# input-selector.net
KiCad netlist of a schematic drawn in EAGLE
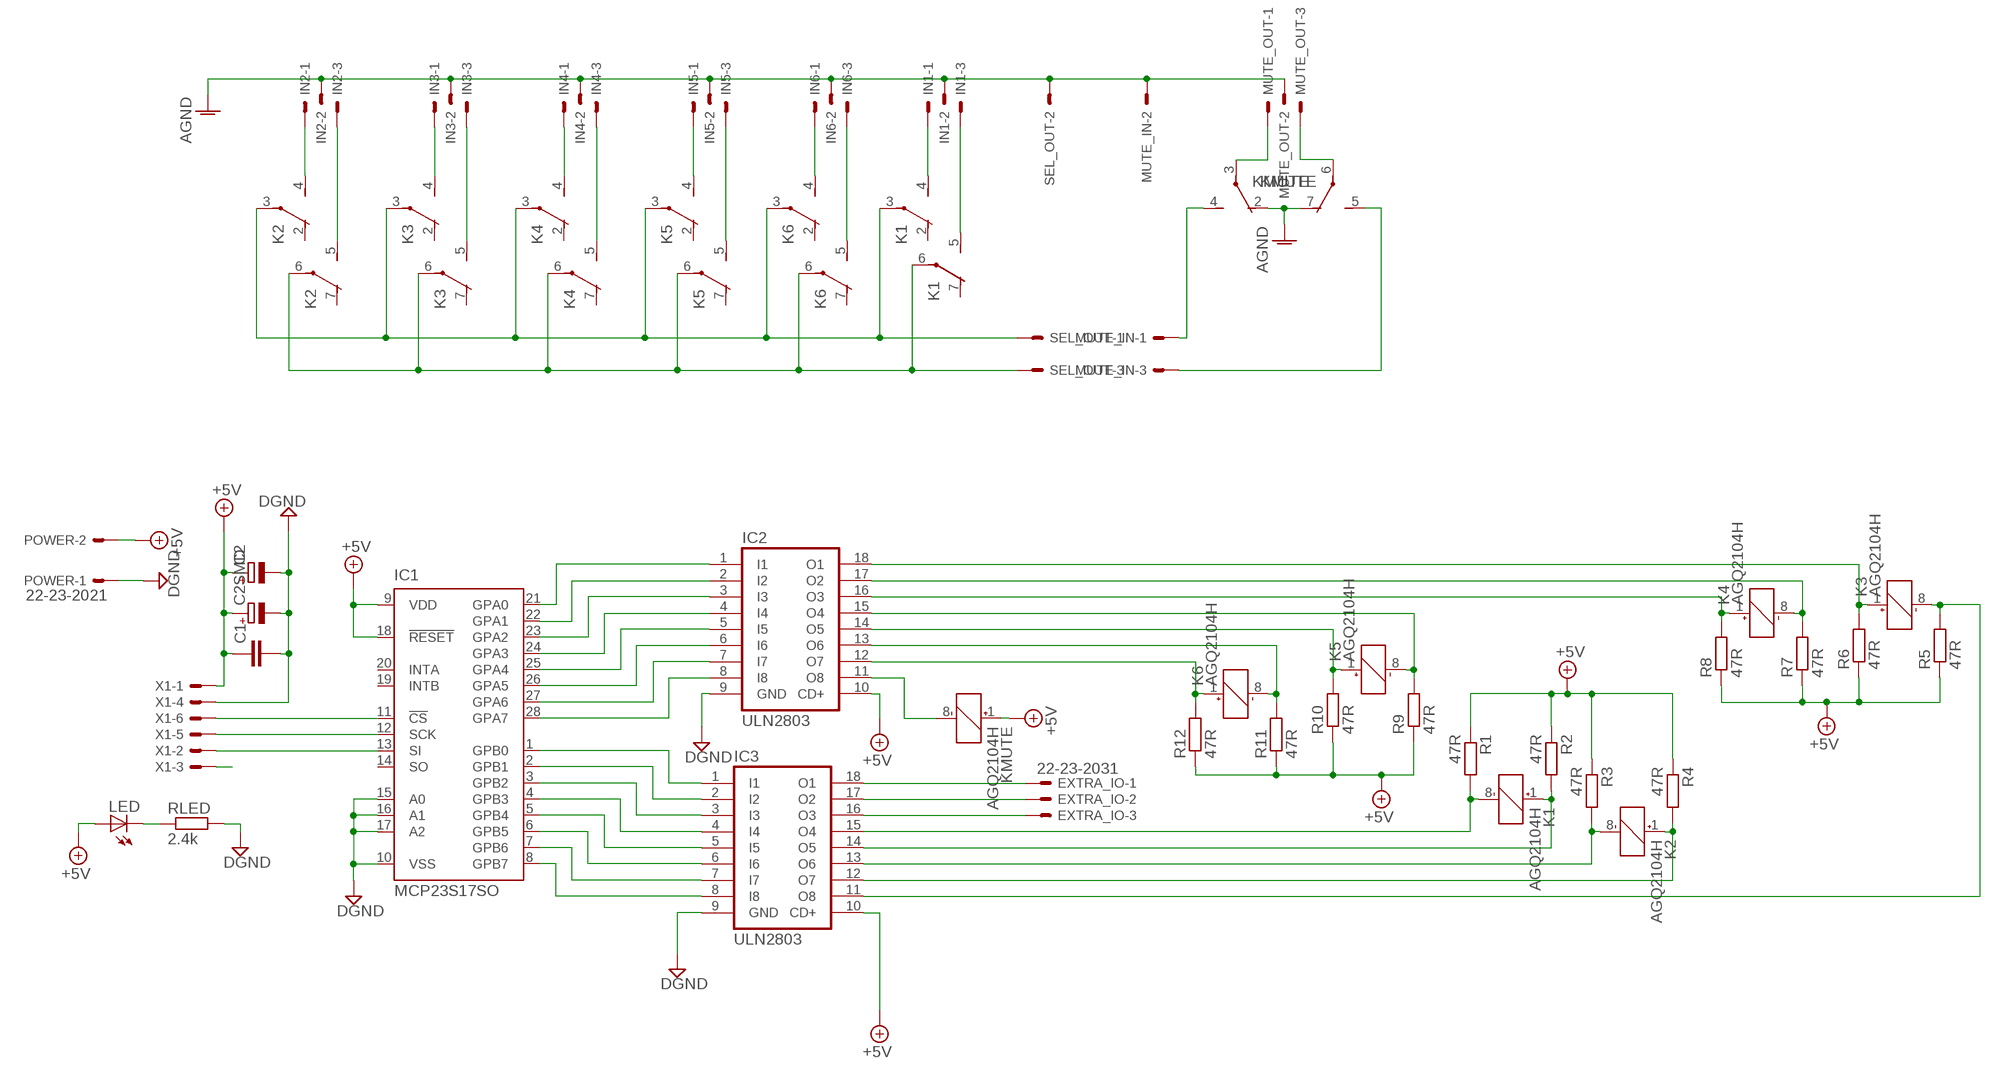
[diagram p0: schematic, sheet 1]

(export (version "E")
  (design (tool "Eeschema 10.0.6"))
  (components
    (comp (ref "C1")
      (value "C-EUC1206")
      (footprint "eagle-import:C1206")
      (libsource (lib "eagle-import") (part "C-EUC1206"))
    )
    (comp (ref "C2")
      (value "CPOL-EUE3.5-8")
      (footprint "eagle-import:E3,5-8")
      (libsource (lib "eagle-import") (part "CPOL-EUE3.5-8"))
    )
    (comp (ref "C2SMD")
      (value "CPOL-EUE")
      (footprint "eagle-import:PANASONIC_E")
      (libsource (lib "eagle-import") (part "CPOL-EUE"))
    )
    (comp (ref "EXTRA_IO")
      (value "22-23-2031")
      (footprint "eagle-import:22-23-2031")
      (fields (field (name "MF") "MOLEX"))
      (libsource (lib "eagle-import") (part "22-23-2031"))
    )
    (comp (ref "IC1")
      (value "MCP23S17SO")
      (footprint "eagle-import:SO28W")
      (fields (field (name "MF") "MICROCHIP") (field (name "MPN") "MCP23S17-E/SO"))
      (libsource (lib "eagle-import") (part "MCP23S17SO"))
    )
    (comp (ref "IC2")
      (value "ULN2803")
      (footprint "eagle-import:SO-18W")
      (libsource (lib "eagle-import") (part "ULN2803ADW"))
    )
    (comp (ref "IC3")
      (value "ULN2803")
      (footprint "eagle-import:SO-18W")
      (libsource (lib "eagle-import") (part "ULN2803ADW"))
    )
    (comp (ref "IN1")
      (value "22-23-2031")
      (footprint "eagle-import:22-23-2031")
      (fields (field (name "MF") "MOLEX"))
      (libsource (lib "eagle-import") (part "22-23-2031"))
    )
    (comp (ref "IN2")
      (value "22-23-2031")
      (footprint "eagle-import:22-23-2031")
      (fields (field (name "MF") "MOLEX"))
      (libsource (lib "eagle-import") (part "22-23-2031"))
    )
    (comp (ref "IN3")
      (value "22-23-2031")
      (footprint "eagle-import:22-23-2031")
      (fields (field (name "MF") "MOLEX"))
      (libsource (lib "eagle-import") (part "22-23-2031"))
    )
    (comp (ref "IN4")
      (value "22-23-2031")
      (footprint "eagle-import:22-23-2031")
      (fields (field (name "MF") "MOLEX"))
      (libsource (lib "eagle-import") (part "22-23-2031"))
    )
    (comp (ref "IN5")
      (value "22-23-2031")
      (footprint "eagle-import:22-23-2031")
      (fields (field (name "MF") "MOLEX"))
      (libsource (lib "eagle-import") (part "22-23-2031"))
    )
    (comp (ref "IN6")
      (value "22-23-2031")
      (footprint "eagle-import:22-23-2031")
      (fields (field (name "MF") "MOLEX"))
      (libsource (lib "eagle-import") (part "22-23-2031"))
    )
    (comp (ref "K1")
      (value "AGQ2104H")
      (footprint "eagle-import:PCBBOARD")
      (libsource (lib "eagle-import") (part "AGQ2104H"))
    )
    (comp (ref "K2")
      (value "AGQ2104H")
      (footprint "eagle-import:PCBBOARD")
      (libsource (lib "eagle-import") (part "AGQ2104H"))
    )
    (comp (ref "K3")
      (value "AGQ2104H")
      (footprint "eagle-import:PCBBOARD")
      (libsource (lib "eagle-import") (part "AGQ2104H"))
    )
    (comp (ref "K4")
      (value "AGQ2104H")
      (footprint "eagle-import:PCBBOARD")
      (libsource (lib "eagle-import") (part "AGQ2104H"))
    )
    (comp (ref "K5")
      (value "AGQ2104H")
      (footprint "eagle-import:PCBBOARD")
      (libsource (lib "eagle-import") (part "AGQ2104H"))
    )
    (comp (ref "K6")
      (value "AGQ2104H")
      (footprint "eagle-import:PCBBOARD")
      (libsource (lib "eagle-import") (part "AGQ2104H"))
    )
    (comp (ref "KMUTE")
      (value "AGQ2104H")
      (footprint "eagle-import:PCBBOARD")
      (libsource (lib "eagle-import") (part "AGQ2104H"))
    )
    (comp (ref "LED")
      (value "LEDSMT1206")
      (footprint "eagle-import:1206")
      (libsource (lib "eagle-import") (part "LEDSMT1206"))
    )
    (comp (ref "MUTE_IN")
      (value "22-23-2031")
      (footprint "eagle-import:22-23-2031")
      (fields (field (name "MF") "MOLEX"))
      (libsource (lib "eagle-import") (part "22-23-2031"))
    )
    (comp (ref "MUTE_OUT")
      (value "22-23-2031")
      (footprint "eagle-import:22-23-2031")
      (fields (field (name "MF") "MOLEX"))
      (libsource (lib "eagle-import") (part "22-23-2031"))
    )
    (comp (ref "POWER")
      (value "22-23-2021")
      (footprint "eagle-import:22-23-2021")
      (fields (field (name "MF") "MOLEX"))
      (libsource (lib "eagle-import") (part "22-23-2021"))
    )
    (comp (ref "R1")
      (value "47R")
      (footprint "eagle-import:R1206")
      (libsource (lib "eagle-import") (part "R-EU_R1206"))
    )
    (comp (ref "R2")
      (value "47R")
      (footprint "eagle-import:R1206")
      (libsource (lib "eagle-import") (part "R-EU_R1206"))
    )
    (comp (ref "R3")
      (value "47R")
      (footprint "eagle-import:R1206")
      (libsource (lib "eagle-import") (part "R-EU_R1206"))
    )
    (comp (ref "R4")
      (value "47R")
      (footprint "eagle-import:R1206")
      (libsource (lib "eagle-import") (part "R-EU_R1206"))
    )
    (comp (ref "R5")
      (value "47R")
      (footprint "eagle-import:R1206")
      (libsource (lib "eagle-import") (part "R-EU_R1206"))
    )
    (comp (ref "R6")
      (value "47R")
      (footprint "eagle-import:R1206")
      (libsource (lib "eagle-import") (part "R-EU_R1206"))
    )
    (comp (ref "R7")
      (value "47R")
      (footprint "eagle-import:R1206")
      (libsource (lib "eagle-import") (part "R-EU_R1206"))
    )
    (comp (ref "R8")
      (value "47R")
      (footprint "eagle-import:R1206")
      (libsource (lib "eagle-import") (part "R-EU_R1206"))
    )
    (comp (ref "R9")
      (value "47R")
      (footprint "eagle-import:R1206")
      (libsource (lib "eagle-import") (part "R-EU_R1206"))
    )
    (comp (ref "R10")
      (value "47R")
      (footprint "eagle-import:R1206")
      (libsource (lib "eagle-import") (part "R-EU_R1206"))
    )
    (comp (ref "R11")
      (value "47R")
      (footprint "eagle-import:R1206")
      (libsource (lib "eagle-import") (part "R-EU_R1206"))
    )
    (comp (ref "R12")
      (value "47R")
      (footprint "eagle-import:R1206")
      (libsource (lib "eagle-import") (part "R-EU_R1206"))
    )
    (comp (ref "RLED")
      (value "2.4k")
      (footprint "eagle-import:R1206")
      (libsource (lib "eagle-import") (part "R-EU_R1206"))
    )
    (comp (ref "SEL_OUT")
      (value "22-23-2031")
      (footprint "eagle-import:22-23-2031")
      (fields (field (name "MF") "MOLEX"))
      (libsource (lib "eagle-import") (part "22-23-2031"))
    )
    (comp (ref "X1")
      (value "22-23-2061")
      (footprint "eagle-import:22-23-2061")
      (fields (field (name "MF") "MOLEX"))
      (libsource (lib "eagle-import") (part "22-23-2061"))
    )
  )
  (nets
    (net (code "1") (name "+5V") (class "Default")
      (node (ref "C1") (pin "1") (pinfunction "1_1") (pintype "passive"))
      (node (ref "C2") (pin "+") (pinfunction "+_+") (pintype "passive"))
      (node (ref "C2SMD") (pin "+") (pinfunction "+_+") (pintype "passive"))
      (node (ref "IC1") (pin "18") (pinfunction "~{RESET}_18") (pintype "input"))
      (node (ref "IC1") (pin "9") (pinfunction "VDD_9") (pintype "power_in"))
      (node (ref "IC2") (pin "10") (pinfunction "CD+_10") (pintype "passive"))
      (node (ref "IC3") (pin "10") (pinfunction "CD+_10") (pintype "passive"))
      (node (ref "KMUTE") (pin "1") (pinfunction "+_1") (pintype "passive"))
      (node (ref "LED") (pin "A") (pinfunction "A_A") (pintype "passive"))
      (node (ref "POWER") (pin "2") (pinfunction "S_2") (pintype "passive"))
      (node (ref "R1") (pin "1") (pinfunction "1_1") (pintype "passive"))
      (node (ref "R10") (pin "1") (pinfunction "1_1") (pintype "passive"))
      (node (ref "R11") (pin "1") (pinfunction "1_1") (pintype "passive"))
      (node (ref "R12") (pin "1") (pinfunction "1_1") (pintype "passive"))
      (node (ref "R2") (pin "1") (pinfunction "1_1") (pintype "passive"))
      (node (ref "R3") (pin "1") (pinfunction "1_1") (pintype "passive"))
      (node (ref "R4") (pin "1") (pinfunction "1_1") (pintype "passive"))
      (node (ref "R5") (pin "1") (pinfunction "1_1") (pintype "passive"))
      (node (ref "R6") (pin "1") (pinfunction "1_1") (pintype "passive"))
      (node (ref "R7") (pin "1") (pinfunction "1_1") (pintype "passive"))
      (node (ref "R8") (pin "1") (pinfunction "1_1") (pintype "passive"))
      (node (ref "R9") (pin "1") (pinfunction "1_1") (pintype "passive"))
      (node (ref "X1") (pin "1") (pinfunction "S_1") (pintype "passive"))
    )
    (net (code "2") (name "AGND") (class "Default")
      (node (ref "IN1") (pin "2") (pinfunction "S_2") (pintype "passive"))
      (node (ref "IN2") (pin "2") (pinfunction "S_2") (pintype "passive"))
      (node (ref "IN3") (pin "2") (pinfunction "S_2") (pintype "passive"))
      (node (ref "IN4") (pin "2") (pinfunction "S_2") (pintype "passive"))
      (node (ref "IN5") (pin "2") (pinfunction "S_2") (pintype "passive"))
      (node (ref "IN6") (pin "2") (pinfunction "S_2") (pintype "passive"))
      (node (ref "KMUTE") (pin "2") (pinfunction "O_2") (pintype "passive"))
      (node (ref "KMUTE") (pin "7") (pinfunction "O_7") (pintype "passive"))
      (node (ref "MUTE_IN") (pin "2") (pinfunction "S_2") (pintype "passive"))
      (node (ref "MUTE_OUT") (pin "2") (pinfunction "S_2") (pintype "passive"))
      (node (ref "SEL_OUT") (pin "2") (pinfunction "S_2") (pintype "passive"))
    )
    (net (code "3") (name "DGND") (class "Default")
      (node (ref "C1") (pin "2") (pinfunction "2_2") (pintype "passive"))
      (node (ref "C2") (pin "-") (pinfunction "-_-") (pintype "passive"))
      (node (ref "C2SMD") (pin "-") (pinfunction "-_-") (pintype "passive"))
      (node (ref "IC1") (pin "10") (pinfunction "VSS_10") (pintype "power_in"))
      (node (ref "IC1") (pin "15") (pinfunction "A0_15") (pintype "input"))
      (node (ref "IC1") (pin "16") (pinfunction "A1_16") (pintype "input"))
      (node (ref "IC1") (pin "17") (pinfunction "A2_17") (pintype "input"))
      (node (ref "IC2") (pin "9") (pinfunction "GND_9") (pintype "power_in"))
      (node (ref "IC3") (pin "9") (pinfunction "GND_9") (pintype "power_in"))
      (node (ref "POWER") (pin "1") (pinfunction "S_1") (pintype "passive"))
      (node (ref "RLED") (pin "2") (pinfunction "2_2") (pintype "passive"))
      (node (ref "X1") (pin "4") (pinfunction "S_4") (pintype "passive"))
    )
    (net (code "4") (name "Net-(EXTRA_IOA-S)") (class "Default")
      (node (ref "EXTRA_IO") (pin "1") (pinfunction "S_1") (pintype "passive"))
      (node (ref "IC3") (pin "18") (pinfunction "O1_18") (pintype "open_collector"))
    )
    (net (code "5") (name "Net-(EXTRA_IOB-S)") (class "Default")
      (node (ref "EXTRA_IO") (pin "2") (pinfunction "S_2") (pintype "passive"))
      (node (ref "IC3") (pin "17") (pinfunction "O2_17") (pintype "open_collector"))
    )
    (net (code "6") (name "Net-(EXTRA_IOC-S)") (class "Default")
      (node (ref "EXTRA_IO") (pin "3") (pinfunction "S_3") (pintype "passive"))
      (node (ref "IC3") (pin "16") (pinfunction "O3_16") (pintype "open_collector"))
    )
    (net (code "7") (name "Net-(IC1-GPA0)") (class "Default")
      (node (ref "IC1") (pin "21") (pinfunction "GPA0_21") (pintype "bidirectional"))
      (node (ref "IC2") (pin "1") (pinfunction "I1_1") (pintype "input"))
    )
    (net (code "8") (name "Net-(IC1-GPA1)") (class "Default")
      (node (ref "IC1") (pin "22") (pinfunction "GPA1_22") (pintype "bidirectional"))
      (node (ref "IC2") (pin "2") (pinfunction "I2_2") (pintype "input"))
    )
    (net (code "9") (name "Net-(IC1-GPA2)") (class "Default")
      (node (ref "IC1") (pin "23") (pinfunction "GPA2_23") (pintype "bidirectional"))
      (node (ref "IC2") (pin "3") (pinfunction "I3_3") (pintype "input"))
    )
    (net (code "10") (name "Net-(IC1-GPA3)") (class "Default")
      (node (ref "IC1") (pin "24") (pinfunction "GPA3_24") (pintype "bidirectional"))
      (node (ref "IC2") (pin "4") (pinfunction "I4_4") (pintype "input"))
    )
    (net (code "11") (name "Net-(IC1-GPA4)") (class "Default")
      (node (ref "IC1") (pin "25") (pinfunction "GPA4_25") (pintype "bidirectional"))
      (node (ref "IC2") (pin "5") (pinfunction "I5_5") (pintype "input"))
    )
    (net (code "12") (name "Net-(IC1-GPA5)") (class "Default")
      (node (ref "IC1") (pin "26") (pinfunction "GPA5_26") (pintype "bidirectional"))
      (node (ref "IC2") (pin "6") (pinfunction "I6_6") (pintype "input"))
    )
    (net (code "13") (name "Net-(IC1-GPA6)") (class "Default")
      (node (ref "IC1") (pin "27") (pinfunction "GPA6_27") (pintype "bidirectional"))
      (node (ref "IC2") (pin "7") (pinfunction "I7_7") (pintype "input"))
    )
    (net (code "14") (name "Net-(IC1-GPA7)") (class "Default")
      (node (ref "IC1") (pin "28") (pinfunction "GPA7_28") (pintype "bidirectional"))
      (node (ref "IC2") (pin "8") (pinfunction "I8_8") (pintype "input"))
    )
    (net (code "15") (name "Net-(IC1-GPB0)") (class "Default")
      (node (ref "IC1") (pin "1") (pinfunction "GPB0_1") (pintype "bidirectional"))
      (node (ref "IC3") (pin "1") (pinfunction "I1_1") (pintype "input"))
    )
    (net (code "16") (name "Net-(IC1-GPB1)") (class "Default")
      (node (ref "IC1") (pin "2") (pinfunction "GPB1_2") (pintype "bidirectional"))
      (node (ref "IC3") (pin "2") (pinfunction "I2_2") (pintype "input"))
    )
    (net (code "17") (name "Net-(IC1-GPB2)") (class "Default")
      (node (ref "IC1") (pin "3") (pinfunction "GPB2_3") (pintype "bidirectional"))
      (node (ref "IC3") (pin "3") (pinfunction "I3_3") (pintype "input"))
    )
    (net (code "18") (name "Net-(IC1-GPB3)") (class "Default")
      (node (ref "IC1") (pin "4") (pinfunction "GPB3_4") (pintype "bidirectional"))
      (node (ref "IC3") (pin "4") (pinfunction "I4_4") (pintype "input"))
    )
    (net (code "19") (name "Net-(IC1-GPB4)") (class "Default")
      (node (ref "IC1") (pin "5") (pinfunction "GPB4_5") (pintype "bidirectional"))
      (node (ref "IC3") (pin "5") (pinfunction "I5_5") (pintype "input"))
    )
    (net (code "20") (name "Net-(IC1-GPB5)") (class "Default")
      (node (ref "IC1") (pin "6") (pinfunction "GPB5_6") (pintype "bidirectional"))
      (node (ref "IC3") (pin "6") (pinfunction "I6_6") (pintype "input"))
    )
    (net (code "21") (name "Net-(IC1-GPB6)") (class "Default")
      (node (ref "IC1") (pin "7") (pinfunction "GPB6_7") (pintype "bidirectional"))
      (node (ref "IC3") (pin "7") (pinfunction "I7_7") (pintype "input"))
    )
    (net (code "22") (name "Net-(IC1-GPB7)") (class "Default")
      (node (ref "IC1") (pin "8") (pinfunction "GPB7_8") (pintype "bidirectional"))
      (node (ref "IC3") (pin "8") (pinfunction "I8_8") (pintype "input"))
    )
    (net (code "23") (name "Net-(IC1-SCK)") (class "Default")
      (node (ref "IC1") (pin "12") (pinfunction "SCK_12") (pintype "input"))
      (node (ref "X1") (pin "5") (pinfunction "S_5") (pintype "passive"))
    )
    (net (code "24") (name "Net-(IC1-SI)") (class "Default")
      (node (ref "IC1") (pin "13") (pinfunction "SI_13") (pintype "input"))
      (node (ref "X1") (pin "2") (pinfunction "S_2") (pintype "passive"))
    )
    (net (code "25") (name "Net-(IC1-~{CS})") (class "Default")
      (node (ref "IC1") (pin "11") (pinfunction "~{CS}_11") (pintype "input"))
      (node (ref "X1") (pin "6") (pinfunction "S_6") (pintype "passive"))
    )
    (net (code "26") (name "Net-(IC2-O1)") (class "Default")
      (node (ref "IC2") (pin "18") (pinfunction "O1_18") (pintype "open_collector"))
      (node (ref "K3") (pin "1") (pinfunction "+_1") (pintype "passive"))
      (node (ref "R6") (pin "2") (pinfunction "2_2") (pintype "passive"))
    )
    (net (code "27") (name "Net-(IC2-O2)") (class "Default")
      (node (ref "IC2") (pin "17") (pinfunction "O2_17") (pintype "open_collector"))
      (node (ref "K4") (pin "8") (pinfunction "-_8") (pintype "passive"))
      (node (ref "R7") (pin "2") (pinfunction "2_2") (pintype "passive"))
    )
    (net (code "28") (name "Net-(IC2-O3)") (class "Default")
      (node (ref "IC2") (pin "16") (pinfunction "O3_16") (pintype "open_collector"))
      (node (ref "K4") (pin "1") (pinfunction "+_1") (pintype "passive"))
      (node (ref "R8") (pin "2") (pinfunction "2_2") (pintype "passive"))
    )
    (net (code "29") (name "Net-(IC2-O4)") (class "Default")
      (node (ref "IC2") (pin "15") (pinfunction "O4_15") (pintype "open_collector"))
      (node (ref "K5") (pin "8") (pinfunction "-_8") (pintype "passive"))
      (node (ref "R9") (pin "2") (pinfunction "2_2") (pintype "passive"))
    )
    (net (code "30") (name "Net-(IC2-O5)") (class "Default")
      (node (ref "IC2") (pin "14") (pinfunction "O5_14") (pintype "open_collector"))
      (node (ref "K5") (pin "1") (pinfunction "+_1") (pintype "passive"))
      (node (ref "R10") (pin "2") (pinfunction "2_2") (pintype "passive"))
    )
    (net (code "31") (name "Net-(IC2-O6)") (class "Default")
      (node (ref "IC2") (pin "13") (pinfunction "O6_13") (pintype "open_collector"))
      (node (ref "K6") (pin "8") (pinfunction "-_8") (pintype "passive"))
      (node (ref "R11") (pin "2") (pinfunction "2_2") (pintype "passive"))
    )
    (net (code "32") (name "Net-(IC2-O7)") (class "Default")
      (node (ref "IC2") (pin "12") (pinfunction "O7_12") (pintype "open_collector"))
      (node (ref "K6") (pin "1") (pinfunction "+_1") (pintype "passive"))
      (node (ref "R12") (pin "2") (pinfunction "2_2") (pintype "passive"))
    )
    (net (code "33") (name "Net-(IC2-O8)") (class "Default")
      (node (ref "IC2") (pin "11") (pinfunction "O8_11") (pintype "open_collector"))
      (node (ref "KMUTE") (pin "8") (pinfunction "-_8") (pintype "passive"))
    )
    (net (code "34") (name "Net-(IC3-O4)") (class "Default")
      (node (ref "IC3") (pin "15") (pinfunction "O4_15") (pintype "open_collector"))
      (node (ref "K1") (pin "8") (pinfunction "-_8") (pintype "passive"))
      (node (ref "R1") (pin "2") (pinfunction "2_2") (pintype "passive"))
    )
    (net (code "35") (name "Net-(IC3-O5)") (class "Default")
      (node (ref "IC3") (pin "14") (pinfunction "O5_14") (pintype "open_collector"))
      (node (ref "K1") (pin "1") (pinfunction "+_1") (pintype "passive"))
      (node (ref "R2") (pin "2") (pinfunction "2_2") (pintype "passive"))
    )
    (net (code "36") (name "Net-(IC3-O6)") (class "Default")
      (node (ref "IC3") (pin "13") (pinfunction "O6_13") (pintype "open_collector"))
      (node (ref "K2") (pin "8") (pinfunction "-_8") (pintype "passive"))
      (node (ref "R3") (pin "2") (pinfunction "2_2") (pintype "passive"))
    )
    (net (code "37") (name "Net-(IC3-O7)") (class "Default")
      (node (ref "IC3") (pin "12") (pinfunction "O7_12") (pintype "open_collector"))
      (node (ref "K2") (pin "1") (pinfunction "+_1") (pintype "passive"))
      (node (ref "R4") (pin "2") (pinfunction "2_2") (pintype "passive"))
    )
    (net (code "38") (name "Net-(IC3-O8)") (class "Default")
      (node (ref "IC3") (pin "11") (pinfunction "O8_11") (pintype "open_collector"))
      (node (ref "K3") (pin "8") (pinfunction "-_8") (pintype "passive"))
      (node (ref "R5") (pin "2") (pinfunction "2_2") (pintype "passive"))
    )
    (net (code "39") (name "Net-(IN1A-S)") (class "Default")
      (node (ref "IN1") (pin "1") (pinfunction "S_1") (pintype "passive"))
      (node (ref "K1") (pin "4") (pinfunction "S_4") (pintype "passive"))
    )
    (net (code "40") (name "Net-(IN1C-S)") (class "Default")
      (node (ref "IN1") (pin "3") (pinfunction "S_3") (pintype "passive"))
      (node (ref "K1") (pin "5") (pinfunction "S_5") (pintype "passive"))
    )
    (net (code "41") (name "Net-(IN2A-S)") (class "Default")
      (node (ref "IN2") (pin "1") (pinfunction "S_1") (pintype "passive"))
      (node (ref "K2") (pin "4") (pinfunction "S_4") (pintype "passive"))
    )
    (net (code "42") (name "Net-(IN2C-S)") (class "Default")
      (node (ref "IN2") (pin "3") (pinfunction "S_3") (pintype "passive"))
      (node (ref "K2") (pin "5") (pinfunction "S_5") (pintype "passive"))
    )
    (net (code "43") (name "Net-(IN3A-S)") (class "Default")
      (node (ref "IN3") (pin "1") (pinfunction "S_1") (pintype "passive"))
      (node (ref "K3") (pin "4") (pinfunction "S_4") (pintype "passive"))
    )
    (net (code "44") (name "Net-(IN3C-S)") (class "Default")
      (node (ref "IN3") (pin "3") (pinfunction "S_3") (pintype "passive"))
      (node (ref "K3") (pin "5") (pinfunction "S_5") (pintype "passive"))
    )
    (net (code "45") (name "Net-(IN4A-S)") (class "Default")
      (node (ref "IN4") (pin "1") (pinfunction "S_1") (pintype "passive"))
      (node (ref "K4") (pin "4") (pinfunction "S_4") (pintype "passive"))
    )
    (net (code "46") (name "Net-(IN4C-S)") (class "Default")
      (node (ref "IN4") (pin "3") (pinfunction "S_3") (pintype "passive"))
      (node (ref "K4") (pin "5") (pinfunction "S_5") (pintype "passive"))
    )
    (net (code "47") (name "Net-(IN5A-S)") (class "Default")
      (node (ref "IN5") (pin "1") (pinfunction "S_1") (pintype "passive"))
      (node (ref "K5") (pin "4") (pinfunction "S_4") (pintype "passive"))
    )
    (net (code "48") (name "Net-(IN5C-S)") (class "Default")
      (node (ref "IN5") (pin "3") (pinfunction "S_3") (pintype "passive"))
      (node (ref "K5") (pin "5") (pinfunction "S_5") (pintype "passive"))
    )
    (net (code "49") (name "Net-(IN6A-S)") (class "Default")
      (node (ref "IN6") (pin "1") (pinfunction "S_1") (pintype "passive"))
      (node (ref "K6") (pin "4") (pinfunction "S_4") (pintype "passive"))
    )
    (net (code "50") (name "Net-(IN6C-S)") (class "Default")
      (node (ref "IN6") (pin "3") (pinfunction "S_3") (pintype "passive"))
      (node (ref "K6") (pin "5") (pinfunction "S_5") (pintype "passive"))
    )
    (net (code "51") (name "Net-(K1B-P)") (class "Default")
      (node (ref "K1") (pin "6") (pinfunction "P_6") (pintype "passive"))
      (node (ref "K2") (pin "6") (pinfunction "P_6") (pintype "passive"))
      (node (ref "K3") (pin "6") (pinfunction "P_6") (pintype "passive"))
      (node (ref "K4") (pin "6") (pinfunction "P_6") (pintype "passive"))
      (node (ref "K5") (pin "6") (pinfunction "P_6") (pintype "passive"))
      (node (ref "K6") (pin "6") (pinfunction "P_6") (pintype "passive"))
      (node (ref "SEL_OUT") (pin "3") (pinfunction "S_3") (pintype "passive"))
    )
    (net (code "52") (name "Net-(K1C-P)") (class "Default")
      (node (ref "K1") (pin "3") (pinfunction "P_3") (pintype "passive"))
      (node (ref "K2") (pin "3") (pinfunction "P_3") (pintype "passive"))
      (node (ref "K3") (pin "3") (pinfunction "P_3") (pintype "passive"))
      (node (ref "K4") (pin "3") (pinfunction "P_3") (pintype "passive"))
      (node (ref "K5") (pin "3") (pinfunction "P_3") (pintype "passive"))
      (node (ref "K6") (pin "3") (pinfunction "P_3") (pintype "passive"))
      (node (ref "SEL_OUT") (pin "1") (pinfunction "S_1") (pintype "passive"))
    )
    (net (code "53") (name "Net-(KMUTEB-P)") (class "Default")
      (node (ref "KMUTE") (pin "6") (pinfunction "P_6") (pintype "passive"))
      (node (ref "MUTE_OUT") (pin "3") (pinfunction "S_3") (pintype "passive"))
    )
    (net (code "54") (name "Net-(KMUTEB-S)") (class "Default")
      (node (ref "KMUTE") (pin "5") (pinfunction "S_5") (pintype "passive"))
      (node (ref "MUTE_IN") (pin "3") (pinfunction "S_3") (pintype "passive"))
    )
    (net (code "55") (name "Net-(KMUTEC-P)") (class "Default")
      (node (ref "KMUTE") (pin "3") (pinfunction "P_3") (pintype "passive"))
      (node (ref "MUTE_OUT") (pin "1") (pinfunction "S_1") (pintype "passive"))
    )
    (net (code "56") (name "Net-(KMUTEC-S)") (class "Default")
      (node (ref "KMUTE") (pin "4") (pinfunction "S_4") (pintype "passive"))
      (node (ref "MUTE_IN") (pin "1") (pinfunction "S_1") (pintype "passive"))
    )
    (net (code "57") (name "Net-(LED-PadC)") (class "Default")
      (node (ref "LED") (pin "C") (pinfunction "C_C") (pintype "passive"))
      (node (ref "RLED") (pin "1") (pinfunction "1_1") (pintype "passive"))
    )
    (net (code "58") (name "unconnected-(IC1-INTA-Pad20)") (class "Default")
      (node (ref "IC1") (pin "20") (pinfunction "INTA_20") (pintype "output"))
    )
    (net (code "59") (name "unconnected-(IC1-INTB-Pad19)") (class "Default")
      (node (ref "IC1") (pin "19") (pinfunction "INTB_19") (pintype "output"))
    )
    (net (code "60") (name "unconnected-(IC1-SO-Pad14)") (class "Default")
      (node (ref "IC1") (pin "14") (pinfunction "SO_14") (pintype "output"))
    )
    (net (code "61") (name "unconnected-(K1B-O-Pad7)") (class "Default")
      (node (ref "K1") (pin "7") (pinfunction "O_7") (pintype "passive"))
    )
    (net (code "62") (name "unconnected-(K1C-O-Pad2)") (class "Default")
      (node (ref "K1") (pin "2") (pinfunction "O_2") (pintype "passive"))
    )
    (net (code "63") (name "unconnected-(K2B-O-Pad7)") (class "Default")
      (node (ref "K2") (pin "7") (pinfunction "O_7") (pintype "passive"))
    )
    (net (code "64") (name "unconnected-(K2C-O-Pad2)") (class "Default")
      (node (ref "K2") (pin "2") (pinfunction "O_2") (pintype "passive"))
    )
    (net (code "65") (name "unconnected-(K3B-O-Pad7)") (class "Default")
      (node (ref "K3") (pin "7") (pinfunction "O_7") (pintype "passive"))
    )
    (net (code "66") (name "unconnected-(K3C-O-Pad2)") (class "Default")
      (node (ref "K3") (pin "2") (pinfunction "O_2") (pintype "passive"))
    )
    (net (code "67") (name "unconnected-(K4B-O-Pad7)") (class "Default")
      (node (ref "K4") (pin "7") (pinfunction "O_7") (pintype "passive"))
    )
    (net (code "68") (name "unconnected-(K4C-O-Pad2)") (class "Default")
      (node (ref "K4") (pin "2") (pinfunction "O_2") (pintype "passive"))
    )
    (net (code "69") (name "unconnected-(K5B-O-Pad7)") (class "Default")
      (node (ref "K5") (pin "7") (pinfunction "O_7") (pintype "passive"))
    )
    (net (code "70") (name "unconnected-(K5C-O-Pad2)") (class "Default")
      (node (ref "K5") (pin "2") (pinfunction "O_2") (pintype "passive"))
    )
    (net (code "71") (name "unconnected-(K6B-O-Pad7)") (class "Default")
      (node (ref "K6") (pin "7") (pinfunction "O_7") (pintype "passive"))
    )
    (net (code "72") (name "unconnected-(K6C-O-Pad2)") (class "Default")
      (node (ref "K6") (pin "2") (pinfunction "O_2") (pintype "passive"))
    )
    (net (code "73") (name "unconnected-(X1C-S-Pad3)") (class "Default")
      (node (ref "X1") (pin "3") (pinfunction "S_3") (pintype "passive"))
    )
  )
)
